# 13_6.net
KiCad netlist of a schematic drawn in Altium Designer
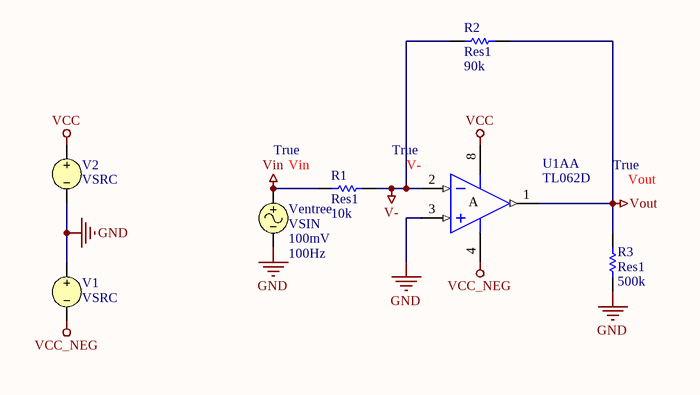
[diagram p0: 13.6.SchDoc]

(export (version "E")
  (design (tool "Eeschema 10.0.6"))
  (components
    (comp (ref "R1")
      (value "Res1")
      (footprint "AXIAL-0.3")
      (description "Resistor")
      (fields (field (name "ALTIUM_VALUE") "10k") (field (name "PUBLISHER") "Altium Limited"))
      (libsource (lib "Miscellaneous Devices") (part "Res1"))
    )
    (comp (ref "R2")
      (value "Res1")
      (footprint "AXIAL-0.3")
      (description "Resistor")
      (fields (field (name "ALTIUM_VALUE") "90k") (field (name "PUBLISHER") "Altium Limited"))
      (libsource (lib "Miscellaneous Devices") (part "Res1"))
    )
    (comp (ref "R3")
      (value "Res1")
      (footprint "AXIAL-0.3")
      (description "Resistor")
      (fields (field (name "ALTIUM_VALUE") "500k") (field (name "PUBLISHER") "Altium Limited"))
      (libsource (lib "Miscellaneous Devices") (part "Res1"))
    )
    (comp (ref "U1A")
      (value "TL062D")
      (footprint "D008_L")
      (description "Low-Power JFET-Input Operational Amplifier")
      (fields (field (name "PUBLISHER") "Altium Limited"))
      (libsource (lib "TI Operational Amplifier") (part "TL062D"))
    )
    (comp (ref "V1")
      (value "VSRC")
      (description "Voltage Source")
      (fields (field (name "PUBLISHER") "Altium Limited"))
      (libsource (lib "Simulation Sources") (part "VSRC"))
    )
    (comp (ref "V2")
      (value "VSRC")
      (description "Voltage Source")
      (fields (field (name "PUBLISHER") "Altium Limited"))
      (libsource (lib "Simulation Sources") (part "VSRC"))
    )
    (comp (ref "Ventree")
      (value "VSIN")
      (description "Sinusoidal Voltage Source")
      (fields
        (field (name "AMPLITUDE") "100mV")
        (field (name "FREQUENCY") "100Hz")
        (field (name "PUBLISHER") "Altium Limited")
      )
      (libsource (lib "Simulation Sources") (part "VSIN"))
    )
  )
  (nets
    (net (code "1") (name "GND") (class "Default")
      (node (ref "R3") (pin "1") (pinfunction "1_1") (pintype "passive"))
      (node (ref "U1A") (pin "3") (pinfunction "IN+_3") (pintype "input"))
      (node (ref "V1") (pin "1") (pinfunction "1_1") (pintype "passive"))
      (node (ref "V2") (pin "2") (pinfunction "2_2") (pintype "passive"))
      (node (ref "Ventree") (pin "2") (pinfunction "2_2") (pintype "passive"))
    )
    (net (code "2") (name "V-") (class "Default")
      (node (ref "R1") (pin "2") (pinfunction "2_2") (pintype "passive"))
      (node (ref "R2") (pin "1") (pinfunction "1_1") (pintype "passive"))
      (node (ref "U1A") (pin "2") (pinfunction "IN-_2") (pintype "input"))
    )
    (net (code "3") (name "VCC") (class "Default")
      (node (ref "U1A") (pin "8") (pinfunction "V+_8") (pintype "power_in"))
      (node (ref "V2") (pin "1") (pinfunction "1_1") (pintype "passive"))
    )
    (net (code "4") (name "VCC_NEG") (class "Default")
      (node (ref "U1A") (pin "4") (pinfunction "V-_4") (pintype "power_in"))
      (node (ref "V1") (pin "2") (pinfunction "2_2") (pintype "passive"))
    )
    (net (code "5") (name "Vin") (class "Default")
      (node (ref "R1") (pin "1") (pinfunction "1_1") (pintype "passive"))
      (node (ref "Ventree") (pin "1") (pinfunction "1_1") (pintype "passive"))
    )
    (net (code "6") (name "Vout") (class "Default")
      (node (ref "R2") (pin "2") (pinfunction "2_2") (pintype "passive"))
      (node (ref "R3") (pin "2") (pinfunction "2_2") (pintype "passive"))
      (node (ref "U1A") (pin "1") (pinfunction "OUT_1") (pintype "output"))
    )
  )
)
